# RFID_Antenna.net
KiCad netlist of a schematic drawn in EAGLE
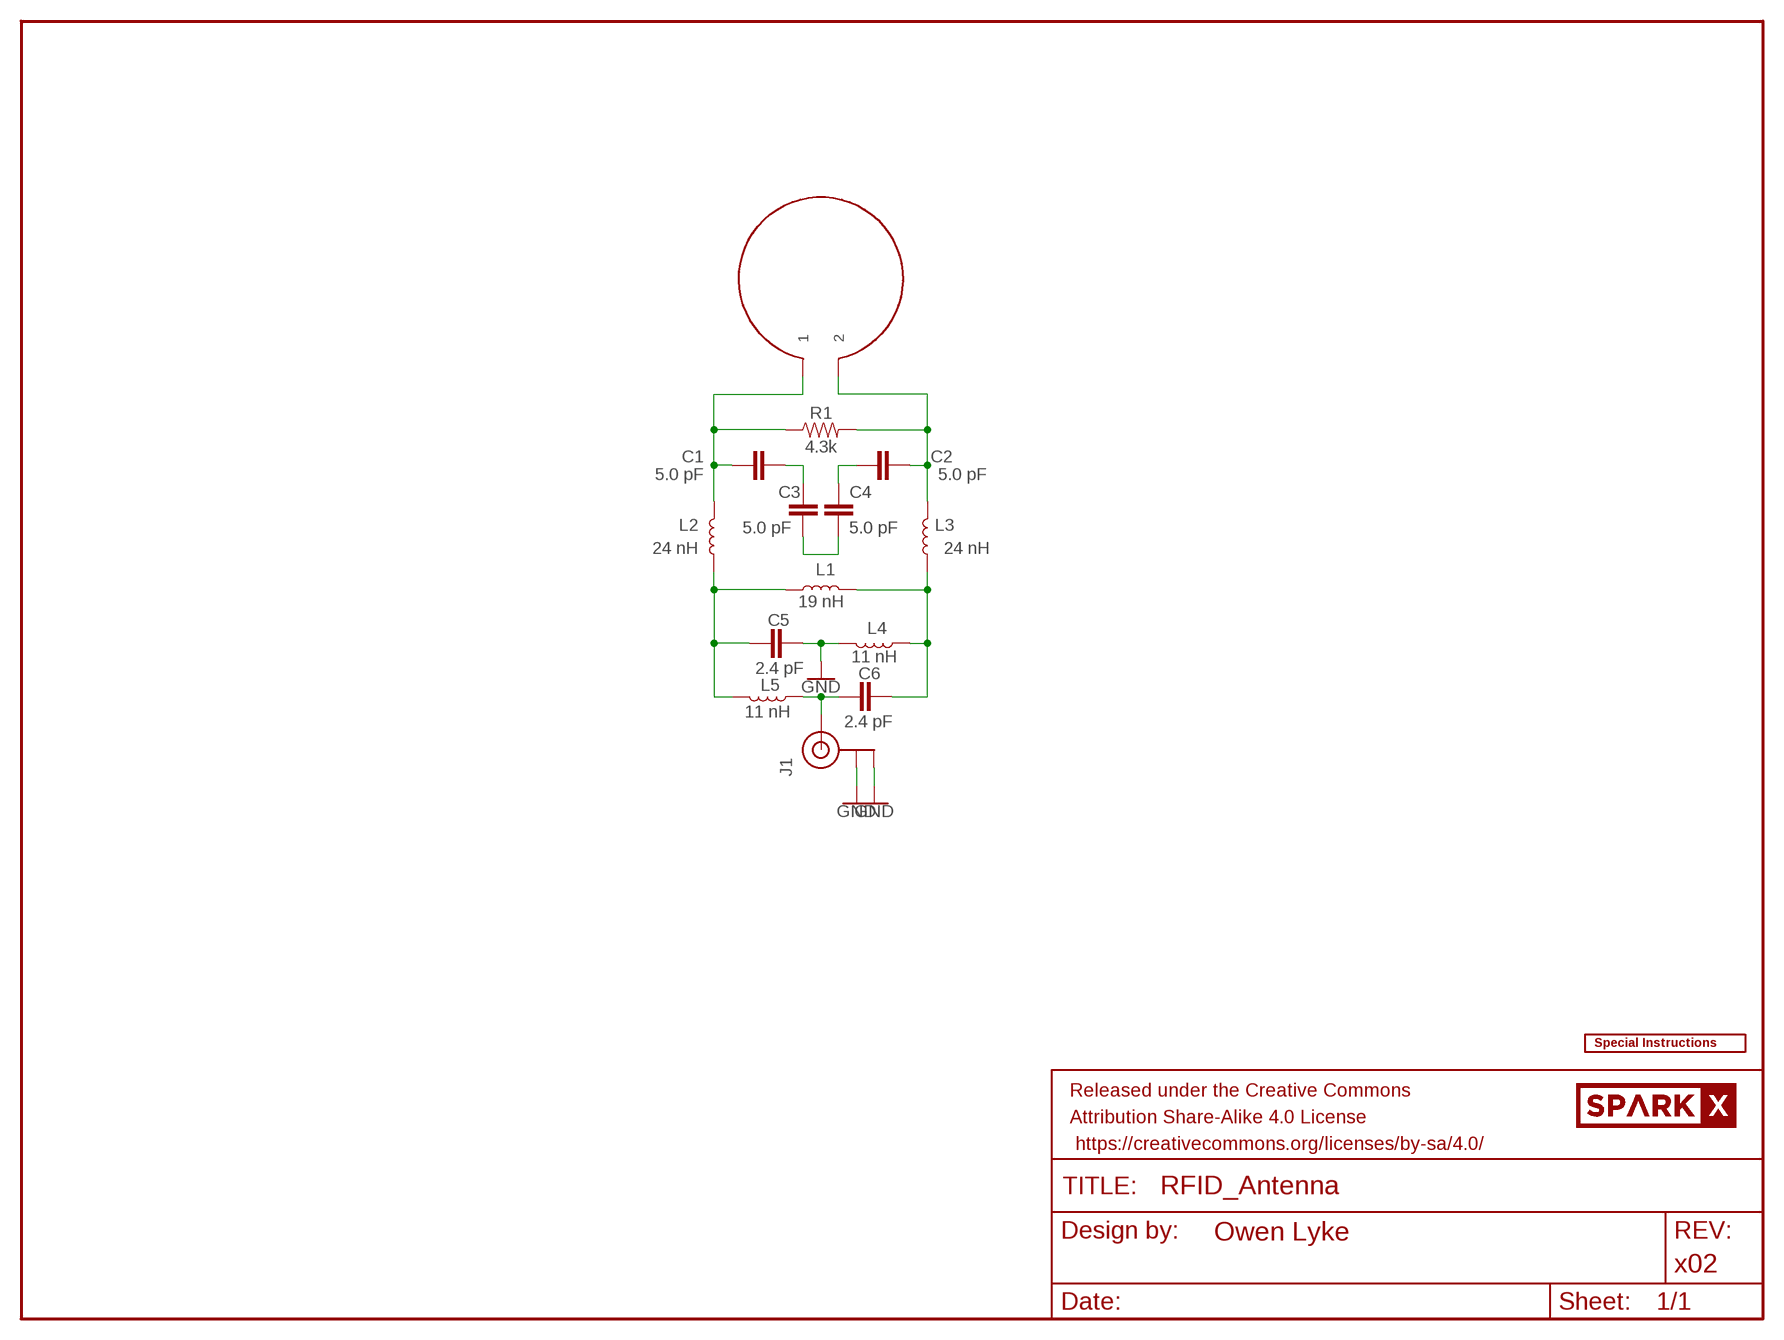
[diagram p0: schematic, sheet 1]

(export (version "E")
  (design (tool "Eeschema 10.0.6"))
  (components
    (comp (ref "C1")
      (value "5.0 pF")
      (footprint "eagle-import:0402_MURATA")
      (libsource (lib "eagle-import") (part "5.0PF-0402"))
    )
    (comp (ref "C2")
      (value "5.0 pF")
      (footprint "eagle-import:0402_MURATA")
      (libsource (lib "eagle-import") (part "5.0PF-0402"))
    )
    (comp (ref "C3")
      (value "5.0 pF")
      (footprint "eagle-import:0402_MURATA")
      (libsource (lib "eagle-import") (part "5.0PF-0402"))
    )
    (comp (ref "C4")
      (value "5.0 pF")
      (footprint "eagle-import:0402_MURATA")
      (libsource (lib "eagle-import") (part "5.0PF-0402"))
    )
    (comp (ref "C5")
      (value "2.4 pF")
      (footprint "eagle-import:0402_MURATA")
      (libsource (lib "eagle-import") (part "2.4PF-0402"))
    )
    (comp (ref "C6")
      (value "2.4 pF")
      (footprint "eagle-import:0402_MURATA")
      (libsource (lib "eagle-import") (part "2.4PF-0402"))
    )
    (comp (ref "FRAME1")
      (value "FRAME-LETTER")
      (footprint "eagle-import:CREATIVE_COMMONS")
      (fields (field (name "DESIGNER") "Owen Lyke") (field (name "REV") "x02"))
      (libsource (lib "eagle-import") (part "FRAME-LETTER"))
    )
    (comp (ref "J1")
      (value "U.FL")
      (footprint "eagle-import:U.FL")
      (libsource (lib "eagle-import") (part "U.FL"))
    )
    (comp (ref "L1")
      (value "19 nH")
      (footprint "eagle-import:0402_MURATA")
      (libsource (lib "eagle-import") (part "19NH-0402"))
    )
    (comp (ref "L2")
      (value "24 nH")
      (footprint "eagle-import:0603_MURATA")
      (libsource (lib "eagle-import") (part "24NH-0603"))
    )
    (comp (ref "L3")
      (value "24 nH")
      (footprint "eagle-import:0603_MURATA")
      (libsource (lib "eagle-import") (part "24NH-0603"))
    )
    (comp (ref "L4")
      (value "11 nH")
      (footprint "eagle-import:0603_MURATA")
      (libsource (lib "eagle-import") (part "11NH-0603"))
    )
    (comp (ref "L5")
      (value "11 nH")
      (footprint "eagle-import:0603_MURATA")
      (libsource (lib "eagle-import") (part "11NH-0603"))
    )
    (comp (ref "R1")
      (value "4.3k")
      (footprint "eagle-import:0402_MURATA")
      (libsource (lib "eagle-import") (part "4.3KOHM-0402"))
    )
    (comp (ref "U$1")
      (value "ANTENNA")
      (footprint "eagle-import:ANT")
      (libsource (lib "eagle-import") (part "ANTENNA"))
    )
    (comp (ref "U$2")
      (value "SPECIAL_INSTRUCTIONS-ORDERING")
      (footprint "eagle-import:ORDERING_INSTRUCTIONS")
      (libsource (lib "eagle-import") (part "SPECIAL_INSTRUCTIONS-ORDERING"))
    )
    (comp (ref "U$12")
      (value "SPARKX-LOGO5")
      (footprint "eagle-import:SPARKX-LARGE")
      (libsource (lib "eagle-import") (part "SPARKX-LOGO5"))
    )
  )
  (nets
    (net (code "1") (name "GND") (class "Default")
      (node (ref "C5") (pin "P$1") (pinfunction "1_P$1") (pintype "passive"))
      (node (ref "J1") (pin "1") (pinfunction "GND_1") (pintype "bidirectional"))
      (node (ref "J1") (pin "2") (pinfunction "GND_2") (pintype "bidirectional"))
      (node (ref "L4") (pin "P$2") (pinfunction "2_P$2") (pintype "passive"))
    )
    (net (code "2") (name "Net-(C1-1)") (class "Default")
      (node (ref "C1") (pin "P$1") (pinfunction "1_P$1") (pintype "passive"))
      (node (ref "L2") (pin "P$2") (pinfunction "2_P$2") (pintype "passive"))
      (node (ref "R1") (pin "P$1") (pinfunction "1_P$1") (pintype "passive"))
      (node (ref "U$1") (pin "P$1") (pinfunction "1_P$1") (pintype "bidirectional"))
      (node (ref "U$1") (pin "P$3") (pinfunction "1_P$3") (pintype "bidirectional"))
    )
    (net (code "3") (name "Net-(C1-2)") (class "Default")
      (node (ref "C1") (pin "P$2") (pinfunction "2_P$2") (pintype "passive"))
      (node (ref "C3") (pin "P$1") (pinfunction "1_P$1") (pintype "passive"))
    )
    (net (code "4") (name "Net-(C2-1)") (class "Default")
      (node (ref "C2") (pin "P$1") (pinfunction "1_P$1") (pintype "passive"))
      (node (ref "C4") (pin "P$1") (pinfunction "1_P$1") (pintype "passive"))
    )
    (net (code "5") (name "Net-(C2-2)") (class "Default")
      (node (ref "C2") (pin "P$2") (pinfunction "2_P$2") (pintype "passive"))
      (node (ref "L3") (pin "P$2") (pinfunction "2_P$2") (pintype "passive"))
      (node (ref "R1") (pin "P$2") (pinfunction "2_P$2") (pintype "passive"))
      (node (ref "U$1") (pin "P$2") (pinfunction "2_P$2") (pintype "bidirectional"))
      (node (ref "U$1") (pin "P$4") (pinfunction "2_P$4") (pintype "bidirectional"))
    )
    (net (code "6") (name "Net-(C3-2)") (class "Default")
      (node (ref "C3") (pin "P$2") (pinfunction "2_P$2") (pintype "passive"))
      (node (ref "C4") (pin "P$2") (pinfunction "2_P$2") (pintype "passive"))
    )
    (net (code "7") (name "Net-(C5-2)") (class "Default")
      (node (ref "C5") (pin "P$2") (pinfunction "2_P$2") (pintype "passive"))
      (node (ref "L1") (pin "P$1") (pinfunction "1_P$1") (pintype "passive"))
      (node (ref "L2") (pin "P$1") (pinfunction "1_P$1") (pintype "passive"))
      (node (ref "L5") (pin "P$2") (pinfunction "2_P$2") (pintype "passive"))
    )
    (net (code "8") (name "Net-(C6-1)") (class "Default")
      (node (ref "C6") (pin "P$1") (pinfunction "1_P$1") (pintype "passive"))
      (node (ref "L1") (pin "P$2") (pinfunction "2_P$2") (pintype "passive"))
      (node (ref "L3") (pin "P$1") (pinfunction "1_P$1") (pintype "passive"))
      (node (ref "L4") (pin "P$1") (pinfunction "1_P$1") (pintype "passive"))
    )
    (net (code "9") (name "Net-(C6-2)") (class "Default")
      (node (ref "C6") (pin "P$2") (pinfunction "2_P$2") (pintype "passive"))
      (node (ref "J1") (pin "FEED") (pinfunction "SIGNAL_FEED") (pintype "bidirectional"))
      (node (ref "L5") (pin "P$1") (pinfunction "1_P$1") (pintype "passive"))
    )
  )
)
